# SCH_CHAITANYANFC_2024-05-25.net
KiCad netlist of a schematic drawn in EasyEDA
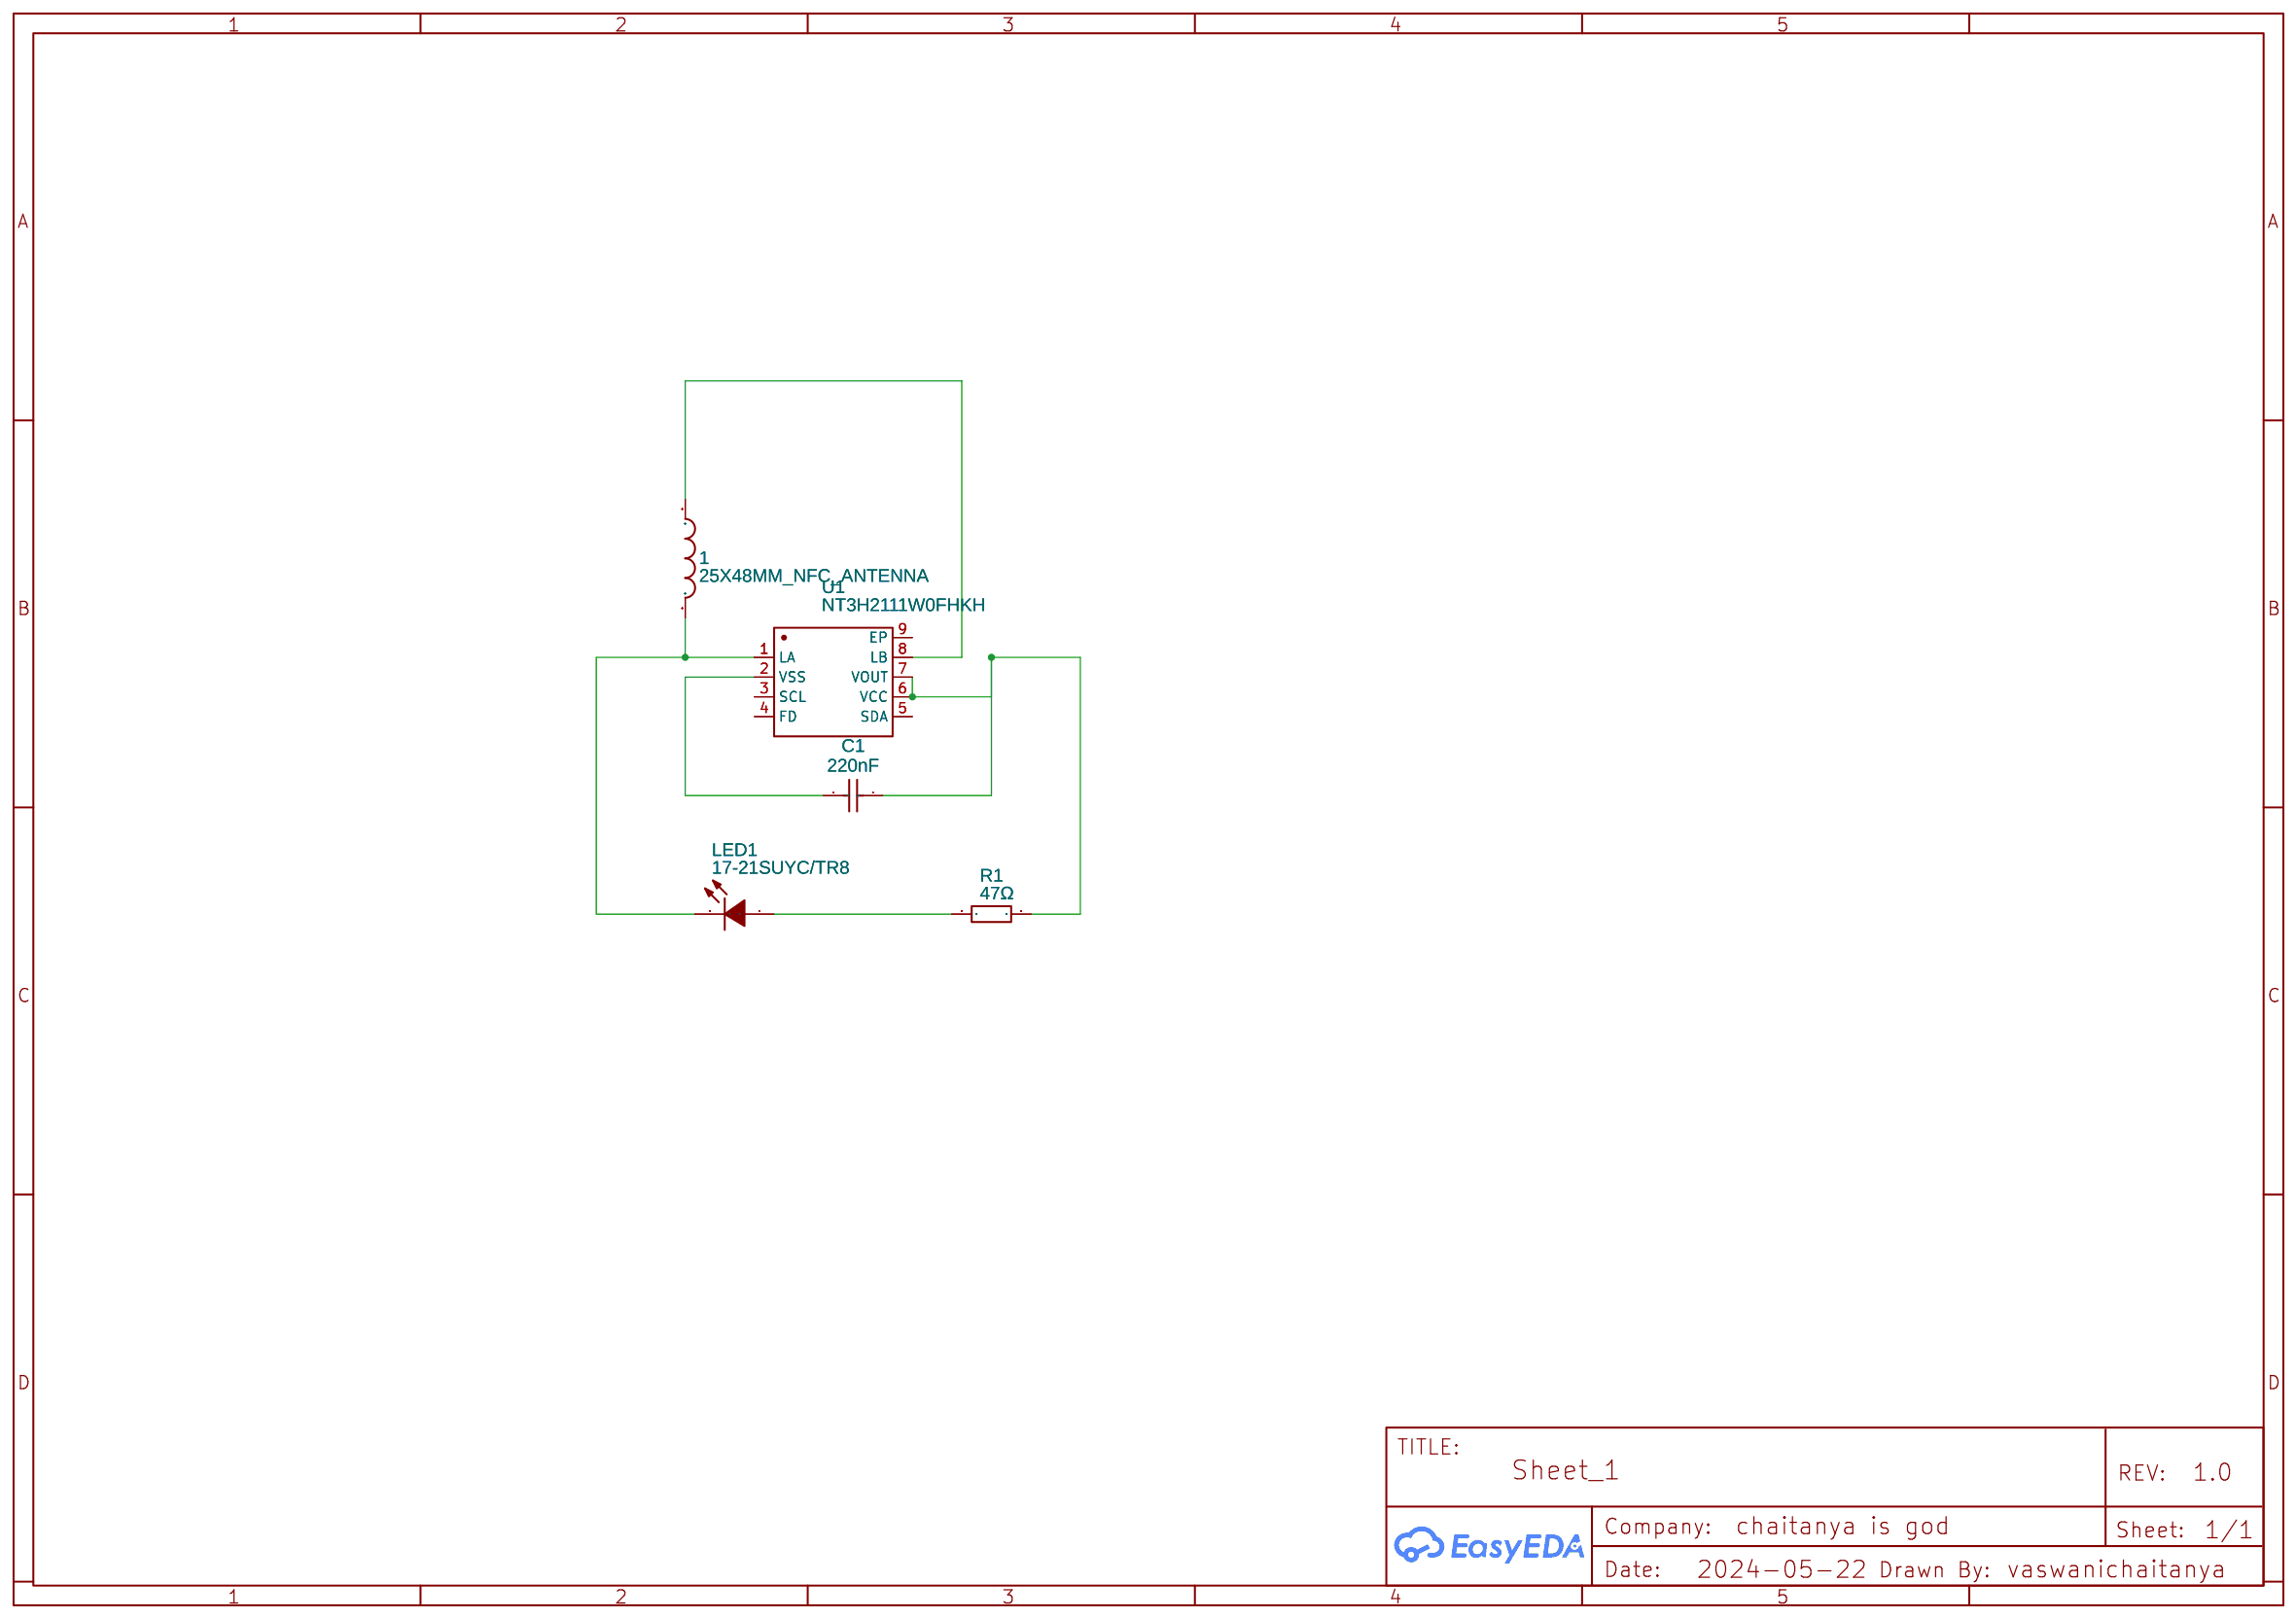
[diagram p0: schematic sheet]

(export (version "E")
  (design (tool "Eeschema 10.0.6"))
  (components
    (comp (ref "1") (value "25X48MM_NFC_ANTENNA") (libsource (lib "") (part "25X48MM_NFC_ANTENNA")))
    (comp (ref "C1")
      (value "220nF")
      (fields (field (name "Manufacturer Part") "CL10B224KA8NNNC") (field (name "Manufacturer") "SAMSUNG"))
      (libsource (lib "") (part "220N CL10B224KA8NNNC"))
    )
    (comp (ref "LED1")
      (value "17-21SUYC/TR8")
      (fields (field (name "Manufacturer Part") "KT-0805黄灯") (field (name "Manufacturer") "KENTO"))
      (libsource (lib "") (part "17-21SUYC/TR8"))
    )
    (comp (ref "R1")
      (value "47Ω")
      (fields
        (field (name "Manufacturer Part") "0603WAF470JT5E")
        (field (name "Manufacturer") "UNI-ROYAL(厚声)")
      )
      (libsource (lib "") (part "0603WAF470JT5E"))
    )
    (comp (ref "U1")
      (value "NT3H2111W0FHKH")
      (fields (field (name "Manufacturer") "NXP(恩智浦)"))
      (libsource (lib "") (part "NT3H2111W0FHKH"))
    )
  )
  (nets
    (net (code "1") (name "Net-(LED1-+)") (class "Default")
      (node (ref "LED1") (pin "1") (pinfunction "+_1") (pintype "unspecified"))
      (node (ref "R1") (pin "1") (pinfunction "1_1") (pintype "input"))
    )
    (net (code "2") (name "Net-(LED1--)") (class "Default")
      (node (ref "1") (pin "P$2") (pinfunction "P$2_P$2") (pintype "bidirectional"))
      (node (ref "LED1") (pin "2") (pinfunction "-_2") (pintype "unspecified"))
      (node (ref "U1") (pin "1") (pinfunction "LA_1") (pintype "unspecified"))
    )
    (net (code "3") (name "Net-(U1-LB)") (class "Default")
      (node (ref "1") (pin "P$1") (pinfunction "P$1_P$1") (pintype "bidirectional"))
      (node (ref "U1") (pin "8") (pinfunction "LB_8") (pintype "unspecified"))
    )
    (net (code "4") (name "Net-(U1-VCC)") (class "Default")
      (node (ref "C1") (pin "2") (pinfunction "2_2") (pintype "input"))
      (node (ref "R1") (pin "2") (pinfunction "2_2") (pintype "input"))
      (node (ref "U1") (pin "6") (pinfunction "VCC_6") (pintype "unspecified"))
      (node (ref "U1") (pin "7") (pinfunction "VOUT_7") (pintype "unspecified"))
    )
    (net (code "5") (name "Net-(U1-VSS)") (class "Default")
      (node (ref "C1") (pin "1") (pinfunction "1_1") (pintype "input"))
      (node (ref "U1") (pin "2") (pinfunction "VSS_2") (pintype "unspecified"))
    )
    (net (code "6") (name "unconnected-(U1-EP-Pad9)") (class "Default")
      (node (ref "U1") (pin "9") (pinfunction "EP_9") (pintype "unspecified"))
    )
    (net (code "7") (name "unconnected-(U1-FD-Pad4)") (class "Default")
      (node (ref "U1") (pin "4") (pinfunction "FD_4") (pintype "unspecified"))
    )
    (net (code "8") (name "unconnected-(U1-SCL-Pad3)") (class "Default")
      (node (ref "U1") (pin "3") (pinfunction "SCL_3") (pintype "unspecified"))
    )
    (net (code "9") (name "unconnected-(U1-SDA-Pad5)") (class "Default")
      (node (ref "U1") (pin "5") (pinfunction "SDA_5") (pintype "unspecified"))
    )
  )
)
